# Central_PCB.net
KiCad netlist of a schematic drawn in Altium Designer
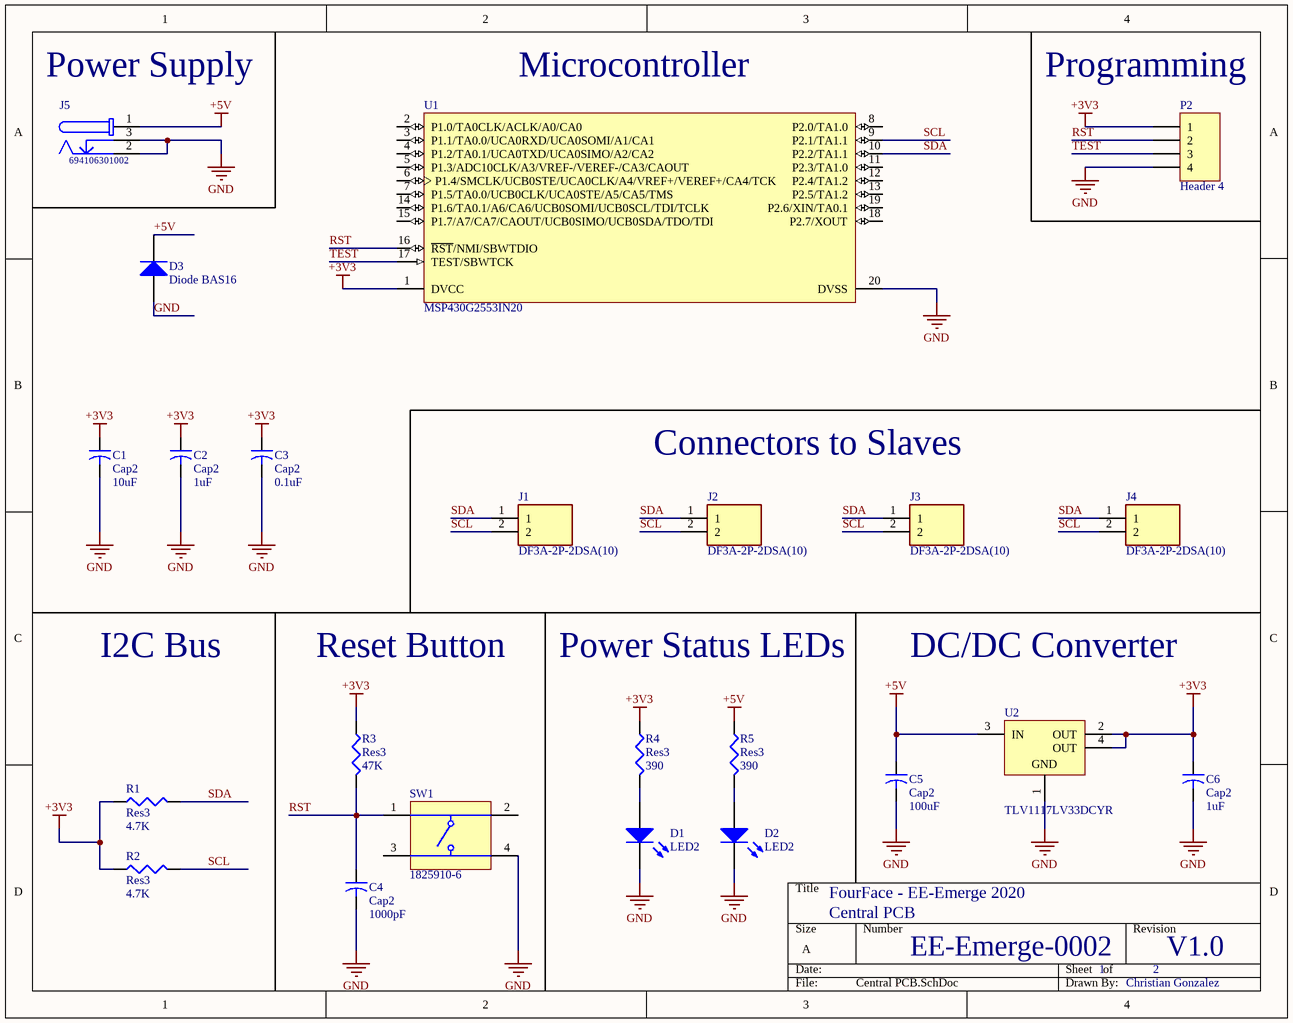
[diagram p0: Central PCB.SchDoc]

(export (version "E")
  (design (tool "Eeschema 10.0.6"))
  (components
    (comp (ref "C1")
      (value "Cap2")
      (footprint "C0805")
      (description "Capacitor")
      (fields (field (name "ALTIUM_VALUE") "10uF") (field (name "PUBLISHER") "Altium Limited"))
      (libsource (lib "EE_Emerge_SkillsProject") (part "Cap2"))
    )
    (comp (ref "C2")
      (value "Cap2")
      (footprint "C0805")
      (description "Capacitor")
      (fields (field (name "ALTIUM_VALUE") "1uF") (field (name "PUBLISHER") "Altium Limited"))
      (libsource (lib "EE_Emerge_SkillsProject") (part "Cap2_4"))
    )
    (comp (ref "C3")
      (value "Cap2")
      (footprint "C0805")
      (description "Capacitor")
      (fields (field (name "ALTIUM_VALUE") "0.1uF") (field (name "PUBLISHER") "Altium Limited"))
      (libsource (lib "EE_Emerge_SkillsProject") (part "Cap2"))
    )
    (comp (ref "C4")
      (value "Cap2")
      (footprint "C0805")
      (description "Capacitor")
      (fields (field (name "ALTIUM_VALUE") "1000pF") (field (name "PUBLISHER") "Altium Limited"))
      (libsource (lib "EE_Emerge_SkillsProject") (part "Cap2"))
    )
    (comp (ref "C5")
      (value "Cap2")
      (footprint "C0805")
      (description "Capacitor")
      (fields (field (name "ALTIUM_VALUE") "100uF") (field (name "PUBLISHER") "Altium Limited"))
      (libsource (lib "PCB_Project_2") (part "Cap2"))
    )
    (comp (ref "C6")
      (value "Cap2")
      (footprint "C0805")
      (description "Capacitor")
      (fields (field (name "ALTIUM_VALUE") "1uF") (field (name "PUBLISHER") "Altium Limited"))
      (libsource (lib "PCB_Project_2") (part "Cap2"))
    )
    (comp (ref "D1")
      (value "LED2")
      (footprint "3.2X1.6X1.1")
      (description "Typical RED, GREEN, YELLOW, AMBER GaAs LED")
      (fields (field (name "PUBLISHER") "Altium Limited"))
      (libsource (lib "PCB_Project_2") (part "LED2"))
    )
    (comp (ref "D2")
      (value "LED2")
      (footprint "3.2X1.6X1.1")
      (description "Typical RED, GREEN, YELLOW, AMBER GaAs LED")
      (fields (field (name "PUBLISHER") "Altium Limited"))
      (libsource (lib "PCB_Project_2") (part "LED2"))
    )
    (comp (ref "D3")
      (value "Diode BAS16")
      (footprint "SOT-23_N")
      (description "Silicon Switching Diode for High-Speed Switching")
      (fields (field (name "PUBLISHER") "Altium Limited"))
      (libsource (lib "Miscellaneous Devices") (part "Diode BAS16"))
    )
    (comp (ref "J1")
      (value "DF3A-2P-2DSA(10)")
      (footprint "SamacSys:SHDR2W50P0X200_1X2_600X500X500P")
      (description "Connector")
      (fields (field (name "MOUSER PART NUMBER") "798-DF3A-2P-2DSA10"))
      (libsource (lib "*") (part "DF3A-2P-2DSA(10)"))
    )
    (comp (ref "J2")
      (value "DF3A-2P-2DSA(10)")
      (footprint "SamacSys:SHDR2W50P0X200_1X2_600X500X500P")
      (description "Connector")
      (fields (field (name "MOUSER PART NUMBER") "798-DF3A-2P-2DSA10"))
      (libsource (lib "*") (part "DF3A-2P-2DSA(10)"))
    )
    (comp (ref "J3")
      (value "DF3A-2P-2DSA(10)")
      (footprint "SamacSys:SHDR2W50P0X200_1X2_600X500X500P")
      (description "Connector")
      (fields (field (name "MOUSER PART NUMBER") "798-DF3A-2P-2DSA10"))
      (libsource (lib "*") (part "DF3A-2P-2DSA(10)"))
    )
    (comp (ref "J4")
      (value "DF3A-2P-2DSA(10)")
      (footprint "SamacSys:SHDR2W50P0X200_1X2_600X500X500P")
      (description "Connector")
      (fields (field (name "MOUSER PART NUMBER") "798-DF3A-2P-2DSA10"))
      (libsource (lib "*") (part "DF3A-2P-2DSA(10)"))
    )
    (comp (ref "J5")
      (value "694106301002")
      (footprint "694106301002")
      (description "DC Power Jack Connector WR-DC, Male, Right Angled, THT, 5 A, 24 V")
      (fields (field (name "MANUFACTURER") "Wurth Elektronik") (field (name "PUBLISHER") "WurthElektronik"))
      (libsource (lib "Altium Content Vault") (part "WE-JACK-2CD3-RN"))
    )
    (comp (ref "P2")
      (value "Header 4")
      (footprint "HDR1X4")
      (description "Header, 4-Pin")
      (fields (field (name "PUBLISHER") "Altium Limited"))
      (libsource (lib "Miscellaneous Connectors") (part "Header 4"))
    )
    (comp (ref "R1")
      (value "Res3")
      (footprint "6-0805_N")
      (description "Resistor")
      (fields (field (name "ALTIUM_VALUE") "4.7K") (field (name "PUBLISHER") "Altium Limited"))
      (libsource (lib "EE_Emerge_SkillsProject") (part "Res3"))
    )
    (comp (ref "R2")
      (value "Res3")
      (footprint "6-0805_N")
      (description "Resistor")
      (fields (field (name "ALTIUM_VALUE") "4.7K") (field (name "PUBLISHER") "Altium Limited"))
      (libsource (lib "EE_Emerge_SkillsProject") (part "Res3"))
    )
    (comp (ref "R3")
      (value "Res3")
      (footprint "6-0805_N")
      (description "Resistor")
      (fields (field (name "ALTIUM_VALUE") "47K") (field (name "PUBLISHER") "Altium Limited"))
      (libsource (lib "EE_Emerge_SkillsProject") (part "Res3"))
    )
    (comp (ref "R4")
      (value "Res3")
      (footprint "6-0805_N")
      (description "Resistor")
      (fields (field (name "ALTIUM_VALUE") "390") (field (name "PUBLISHER") "Altium Limited"))
      (libsource (lib "EE_Emerge_SkillsProject") (part "Res3"))
    )
    (comp (ref "R5")
      (value "Res3")
      (footprint "6-0805_N")
      (description "Resistor")
      (fields (field (name "ALTIUM_VALUE") "390") (field (name "PUBLISHER") "Altium Limited"))
      (libsource (lib "EE_Emerge_SkillsProject") (part "Res3"))
    )
    (comp (ref "SW1")
      (value "1825910-6")
      (footprint "TECO-1825910-6_V")
      (description "Tact Switch, SPST-NO, 0.05 A, -35 to 85 degC, 4-Pin THD, RoHS, Bulk")
      (fields (field (name "MANUFACTURER") "TE Connectivity"))
      (libsource (lib "Altium Content Vault") (part "SW-SPST-4_A"))
    )
    (comp (ref "U1")
      (value "MSP430G2553IN20")
      (footprint "N0020A")
      (fields (field (name "MANUFACTURER") "Texas Instruments"))
      (libsource (lib "PCB_Project_2") (part "CMP-0365-00184-2"))
    )
    (comp (ref "U2")
      (value "TLV1117LV33DCYR")
      (footprint "DCY0004A_N")
      (fields (field (name "MANUFACTURER") "Texas Instruments"))
      (libsource (lib "Altium Content Vault") (part "TI-TLV1117LV33DCY4"))
    )
  )
  (nets
    (net (code "1") (name "+3V3") (class "Default")
      (node (ref "C1") (pin "1") (pinfunction "1_1") (pintype "passive"))
      (node (ref "C2") (pin "1") (pinfunction "1_1") (pintype "passive"))
      (node (ref "C3") (pin "1") (pinfunction "1_1") (pintype "passive"))
      (node (ref "C6") (pin "1") (pinfunction "1_1") (pintype "passive"))
      (node (ref "P2") (pin "1") (pinfunction "1_1") (pintype "passive"))
      (node (ref "R1") (pin "1") (pinfunction "1_1") (pintype "passive"))
      (node (ref "R2") (pin "1") (pinfunction "1_1") (pintype "passive"))
      (node (ref "R3") (pin "1") (pinfunction "1_1") (pintype "passive"))
      (node (ref "R4") (pin "1") (pinfunction "1_1") (pintype "passive"))
      (node (ref "U1") (pin "1") (pinfunction "DVCC_1") (pintype "power_in"))
      (node (ref "U2") (pin "2") (pinfunction "OUT_2") (pintype "power_in"))
      (node (ref "U2") (pin "4") (pinfunction "OUT_4") (pintype "power_in"))
    )
    (net (code "2") (name "+5V") (class "Default")
      (node (ref "C5") (pin "1") (pinfunction "1_1") (pintype "passive"))
      (node (ref "D3") (pin "3") (pinfunction "K_3") (pintype "passive"))
      (node (ref "J5") (pin "1") (pinfunction "1_1") (pintype "passive"))
      (node (ref "R5") (pin "1") (pinfunction "1_1") (pintype "passive"))
      (node (ref "U2") (pin "3") (pinfunction "IN_3") (pintype "power_in"))
    )
    (net (code "3") (name "/RST") (class "Default")
      (node (ref "C4") (pin "1") (pinfunction "1_1") (pintype "passive"))
      (node (ref "P2") (pin "2") (pinfunction "2_2") (pintype "passive"))
      (node (ref "R3") (pin "2") (pinfunction "2_2") (pintype "passive"))
      (node (ref "SW1") (pin "1") (pinfunction "1_1") (pintype "passive"))
      (node (ref "U1") (pin "16") (pinfunction "~{RST}/NMI/SBWTDIO_16") (pintype "bidirectional"))
    )
    (net (code "4") (name "/SCL") (class "Default")
      (node (ref "J1") (pin "2") (pinfunction "2_2") (pintype "passive"))
      (node (ref "J2") (pin "2") (pinfunction "2_2") (pintype "passive"))
      (node (ref "J3") (pin "2") (pinfunction "2_2") (pintype "passive"))
      (node (ref "J4") (pin "2") (pinfunction "2_2") (pintype "passive"))
      (node (ref "R2") (pin "2") (pinfunction "2_2") (pintype "passive"))
      (node (ref "U1") (pin "9") (pinfunction "P2.1/TA1.1_9") (pintype "bidirectional"))
    )
    (net (code "5") (name "/SDA") (class "Default")
      (node (ref "J1") (pin "1") (pinfunction "1_1") (pintype "passive"))
      (node (ref "J2") (pin "1") (pinfunction "1_1") (pintype "passive"))
      (node (ref "J3") (pin "1") (pinfunction "1_1") (pintype "passive"))
      (node (ref "J4") (pin "1") (pinfunction "1_1") (pintype "passive"))
      (node (ref "R1") (pin "2") (pinfunction "2_2") (pintype "passive"))
      (node (ref "U1") (pin "10") (pinfunction "P2.2/TA1.1_10") (pintype "bidirectional"))
    )
    (net (code "6") (name "/TEST") (class "Default")
      (node (ref "P2") (pin "3") (pinfunction "3_3") (pintype "passive"))
      (node (ref "U1") (pin "17") (pinfunction "TEST/SBWTCK_17") (pintype "input"))
    )
    (net (code "7") (name "GND") (class "Default")
      (node (ref "C1") (pin "2") (pinfunction "2_2") (pintype "passive"))
      (node (ref "C2") (pin "2") (pinfunction "2_2") (pintype "passive"))
      (node (ref "C3") (pin "2") (pinfunction "2_2") (pintype "passive"))
      (node (ref "C4") (pin "2") (pinfunction "2_2") (pintype "passive"))
      (node (ref "C5") (pin "2") (pinfunction "2_2") (pintype "passive"))
      (node (ref "C6") (pin "2") (pinfunction "2_2") (pintype "passive"))
      (node (ref "D1") (pin "2") (pinfunction "K_2") (pintype "passive"))
      (node (ref "D2") (pin "2") (pinfunction "K_2") (pintype "passive"))
      (node (ref "D3") (pin "1") (pinfunction "A_1") (pintype "passive"))
      (node (ref "J5") (pin "2") (pinfunction "2_2") (pintype "passive"))
      (node (ref "J5") (pin "3") (pinfunction "3_3") (pintype "passive"))
      (node (ref "P2") (pin "4") (pinfunction "4_4") (pintype "passive"))
      (node (ref "SW1") (pin "4") (pinfunction "4_4") (pintype "passive"))
      (node (ref "U1") (pin "20") (pinfunction "DVSS_20") (pintype "power_in"))
      (node (ref "U2") (pin "1") (pinfunction "GND_1") (pintype "power_in"))
    )
    (net (code "8") (name "Net-(D1-A)") (class "Default")
      (node (ref "D1") (pin "1") (pinfunction "A_1") (pintype "passive"))
      (node (ref "R4") (pin "2") (pinfunction "2_2") (pintype "passive"))
    )
    (net (code "9") (name "Net-(D2-A)") (class "Default")
      (node (ref "D2") (pin "1") (pinfunction "A_1") (pintype "passive"))
      (node (ref "R5") (pin "2") (pinfunction "2_2") (pintype "passive"))
    )
    (net (code "10") (name "unconnected-(SW1-Pad2)") (class "Default")
      (node (ref "SW1") (pin "2") (pinfunction "2_2") (pintype "passive"))
    )
    (net (code "11") (name "unconnected-(SW1-Pad3)") (class "Default")
      (node (ref "SW1") (pin "3") (pinfunction "3_3") (pintype "passive"))
    )
    (net (code "12") (name "unconnected-(U1-P1.0{slash}TA0CLK{slash}ACLK{slash}A0{slash}CA0-Pad2)") (class "Default")
      (node (ref "U1") (pin "2") (pinfunction "P1.0/TA0CLK/ACLK/A0/CA0_2") (pintype "bidirectional"))
    )
    (net (code "13") (name "unconnected-(U1-P1.1{slash}TA0.0{slash}UCA0RXD{slash}UCA0SOMI{slash}A1{slash}CA1-Pad3)") (class "Default")
      (node (ref "U1") (pin "3") (pinfunction "P1.1/TA0.0/UCA0RXD/UCA0SOMI/A1/CA1_3") (pintype "bidirectional"))
    )
    (net (code "14") (name "unconnected-(U1-P1.2{slash}TA0.1{slash}UCA0TXD{slash}UCA0SIMO{slash}A2{slash}CA2-Pad4)") (class "Default")
      (node (ref "U1") (pin "4") (pinfunction "P1.2/TA0.1/UCA0TXD/UCA0SIMO/A2/CA2_4") (pintype "bidirectional"))
    )
    (net (code "15") (name "unconnected-(U1-P1.3{slash}ADC10CLK{slash}A3{slash}VREF-{slash}VEREF-{slash}CA3{slash}CAOUT-Pad5)") (class "Default")
      (node (ref "U1") (pin "5") (pinfunction "P1.3/ADC10CLK/A3/VREF-/VEREF-/CA3/CAOUT_5") (pintype "bidirectional"))
    )
    (net (code "16") (name "unconnected-(U1-P1.4{slash}SMCLK{slash}UCB0STE{slash}UCA0CLK{slash}A4{slash}VREF+{slash}VEREF+{slash}CA4{slash}TCK-Pad6)") (class "Default")
      (node (ref "U1") (pin "6") (pinfunction "P1.4/SMCLK/UCB0STE/UCA0CLK/A4/VREF+/VEREF+/CA4/TCK_6") (pintype "bidirectional"))
    )
    (net (code "17") (name "unconnected-(U1-P1.5{slash}TA0.0{slash}UCB0CLK{slash}UCA0STE{slash}A5{slash}CA5{slash}TMS-Pad7)") (class "Default")
      (node (ref "U1") (pin "7") (pinfunction "P1.5/TA0.0/UCB0CLK/UCA0STE/A5/CA5/TMS_7") (pintype "bidirectional"))
    )
    (net (code "18") (name "unconnected-(U1-P1.6{slash}TA0.1{slash}A6{slash}CA6{slash}UCB0SOMI{slash}UCB0SCL{slash}TDI{slash}TCLK-Pad14)") (class "Default")
      (node (ref "U1") (pin "14") (pinfunction "P1.6/TA0.1/A6/CA6/UCB0SOMI/UCB0SCL/TDI/TCLK_14") (pintype "bidirectional"))
    )
    (net (code "19") (name "unconnected-(U1-P1.7{slash}A7{slash}CA7{slash}CAOUT{slash}UCB0SIMO{slash}UCB0SDA{slash}TDO{slash}TDI-Pad15)") (class "Default")
      (node (ref "U1") (pin "15") (pinfunction "P1.7/A7/CA7/CAOUT/UCB0SIMO/UCB0SDA/TDO/TDI_15") (pintype "bidirectional"))
    )
    (net (code "20") (name "unconnected-(U1-P2.0{slash}TA1.0-Pad8)") (class "Default")
      (node (ref "U1") (pin "8") (pinfunction "P2.0/TA1.0_8") (pintype "bidirectional"))
    )
    (net (code "21") (name "unconnected-(U1-P2.3{slash}TA1.0-Pad11)") (class "Default")
      (node (ref "U1") (pin "11") (pinfunction "P2.3/TA1.0_11") (pintype "bidirectional"))
    )
    (net (code "22") (name "unconnected-(U1-P2.4{slash}TA1.2-Pad12)") (class "Default")
      (node (ref "U1") (pin "12") (pinfunction "P2.4/TA1.2_12") (pintype "bidirectional"))
    )
    (net (code "23") (name "unconnected-(U1-P2.5{slash}TA1.2-Pad13)") (class "Default")
      (node (ref "U1") (pin "13") (pinfunction "P2.5/TA1.2_13") (pintype "bidirectional"))
    )
    (net (code "24") (name "unconnected-(U1-P2.6{slash}XIN{slash}TA0.1-Pad19)") (class "Default")
      (node (ref "U1") (pin "19") (pinfunction "P2.6/XIN/TA0.1_19") (pintype "bidirectional"))
    )
    (net (code "25") (name "unconnected-(U1-P2.7{slash}XOUT-Pad18)") (class "Default")
      (node (ref "U1") (pin "18") (pinfunction "P2.7/XOUT_18") (pintype "bidirectional"))
    )
  )
)
